# Main.net
KiCad netlist of a schematic drawn in Altium Designer
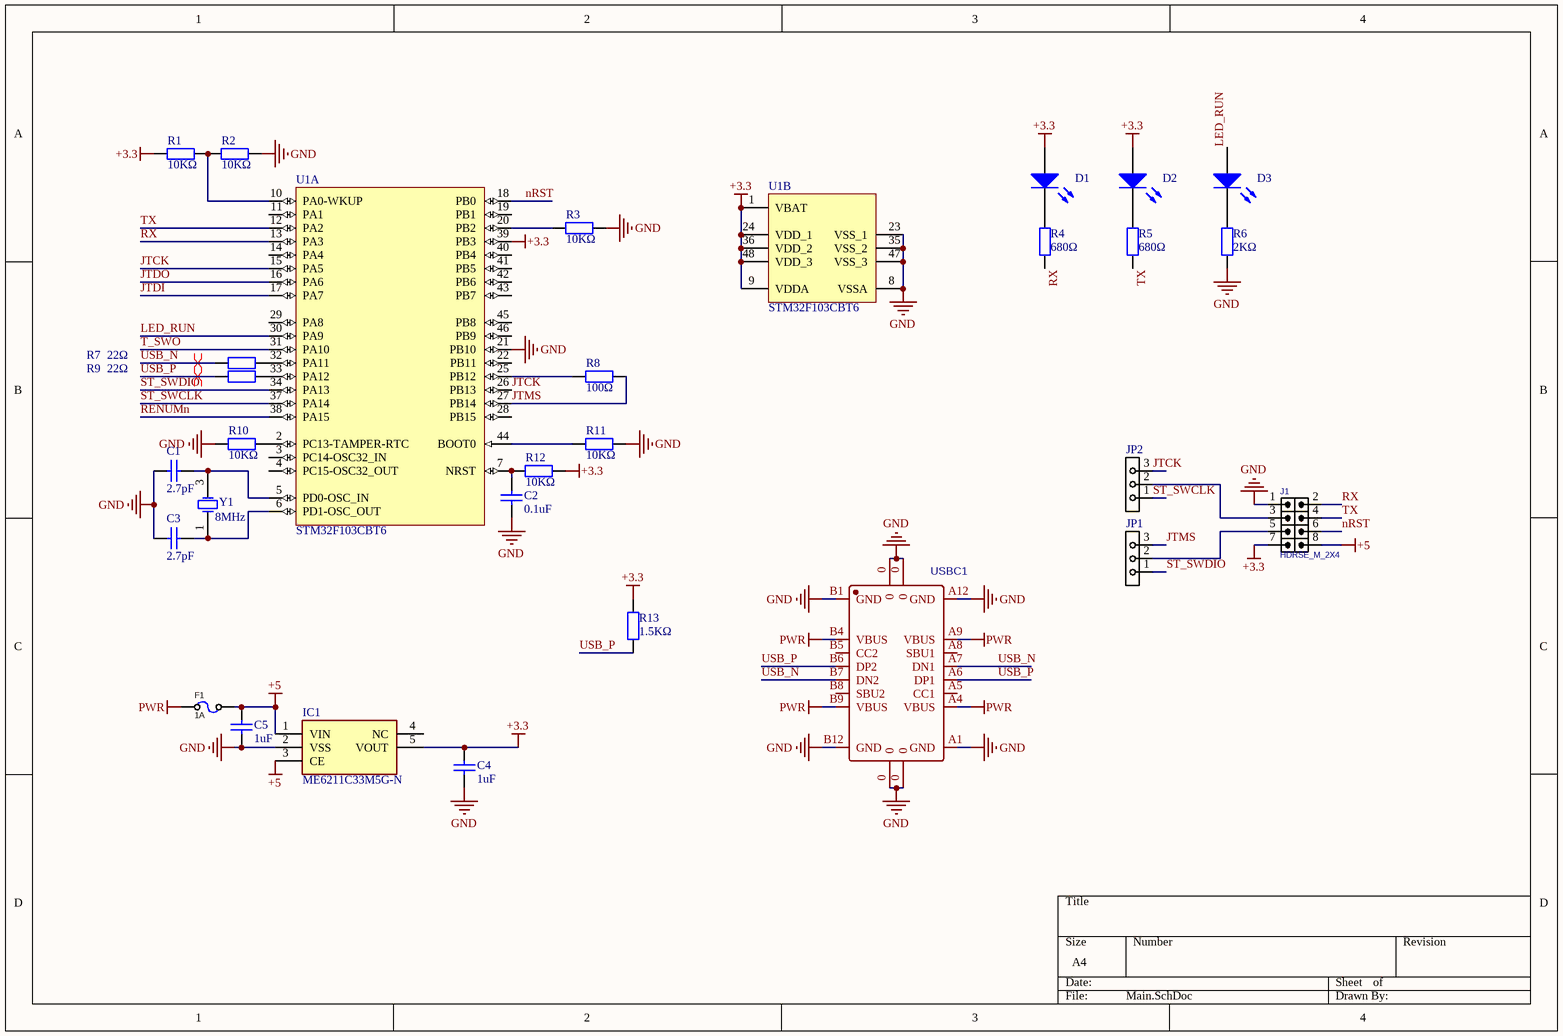
[diagram p0: Main.SchDoc]

(export (version "E")
  (design (tool "Eeschema 10.0.6"))
  (components
    (comp (ref "C1")
      (value "2.7pF")
      (footprint "0603_C")
      (description "贴片电容")
      (libsource (lib "Gaby's Workspace") (part "Symbol"))
    )
    (comp (ref "C2")
      (value "0.1uF")
      (footprint "0603_C")
      (description "贴片电容")
      (libsource (lib "Gaby's Workspace") (part "Symbol"))
    )
    (comp (ref "C3")
      (value "2.7pF")
      (footprint "0603_C")
      (description "贴片电容")
      (libsource (lib "Gaby's Workspace") (part "Symbol"))
    )
    (comp (ref "C4")
      (value "1uF")
      (footprint "0603_C")
      (description "贴片电容")
      (libsource (lib "Gaby's Workspace") (part "Symbol"))
    )
    (comp (ref "C5")
      (value "1uF")
      (footprint "0603_C")
      (description "贴片电容")
      (libsource (lib "Gaby's Workspace") (part "Symbol"))
    )
    (comp (ref "D1")
      (value "~")
      (footprint "0603_LED_S1")
      (description "发光二极管")
      (libsource (lib "") (part "Symbol_2"))
    )
    (comp (ref "D2")
      (value "~")
      (footprint "0603_LED_S1")
      (description "发光二极管")
      (libsource (lib "") (part "Symbol_2"))
    )
    (comp (ref "D3")
      (value "~")
      (footprint "0603_LED_S1")
      (description "发光二极管")
      (libsource (lib "") (part "Symbol_2"))
    )
    (comp (ref "F1")
      (value "1A")
      (footprint "F0805")
      (fields
        (field (name "MANF") "MANF")
        (field (name "MANF_P#") "MANF_PART#")
        (field (name "SOURCE") "protect_tvs_esd_fuse.SchLib")
      )
      (libsource (lib "") (part "Symbol_5"))
    )
    (comp (ref "IC1")
      (value "ME6211C33M5G-N")
      (footprint "SOT95P270X145-5N")
      (description "Integrated Circuit")
      (libsource (lib "Gaby's Workspace") (part "ME6211C33M5G-N"))
    )
    (comp (ref "J1")
      (value "HDRSE_M_2X4")
      (footprint "HDRSE_M_2X4")
      (description "CONN, HEADER, Male, pitch: 2.54mm, 8POS")
      (fields
        (field (name "MANF_P#") "MANF_PART#")
        (field (name "MANF") "MANF")
        (field (name "SOURCE") "conn_header_2.54_st_smd_edge.SchLib")
      )
      (libsource (lib "Gaby's Workspace") (part "HDRSE_M_2X4"))
    )
    (comp (ref "JP1")
      (value "JUMPER_SOLDER_3P")
      (footprint "JP_3_60W")
      (description "JUMPER, HEADER 3PIN")
      (fields (field (name "MANF") "MANF") (field (name "MANF_P#") "MANF_P#"))
      (libsource (lib "") (part "Symbol_7"))
    )
    (comp (ref "JP2")
      (value "JUMPER_SOLDER_3P")
      (footprint "JP_3_60W")
      (description "JUMPER, HEADER 3PIN")
      (fields (field (name "MANF") "MANF") (field (name "MANF_P#") "MANF_P#"))
      (libsource (lib "") (part "Symbol_7"))
    )
    (comp (ref "R1")
      (value "10KΩ")
      (footprint "0603_R")
      (description "贴片电阻")
      (libsource (lib "") (part "Symbol_3"))
    )
    (comp (ref "R2")
      (value "10KΩ")
      (footprint "0603_R")
      (description "贴片电阻")
      (libsource (lib "") (part "Symbol_3"))
    )
    (comp (ref "R3")
      (value "10KΩ")
      (footprint "0603_R")
      (description "贴片电阻")
      (libsource (lib "") (part "Symbol_3"))
    )
    (comp (ref "R4")
      (value "680Ω")
      (footprint "0603_R")
      (description "贴片电阻")
      (libsource (lib "") (part "Symbol_4"))
    )
    (comp (ref "R5")
      (value "680Ω")
      (footprint "0603_R")
      (description "贴片电阻")
      (libsource (lib "") (part "Symbol_4"))
    )
    (comp (ref "R6")
      (value "2KΩ")
      (footprint "0603_R")
      (description "贴片电阻")
      (libsource (lib "") (part "Symbol_4"))
    )
    (comp (ref "R7")
      (value "22Ω")
      (footprint "0603_R")
      (description "贴片电阻")
      (libsource (lib "") (part "Symbol_3"))
    )
    (comp (ref "R8")
      (value "100Ω")
      (footprint "0603_R")
      (description "贴片电阻")
      (libsource (lib "") (part "Symbol_3"))
    )
    (comp (ref "R9")
      (value "22Ω")
      (footprint "0603_R")
      (description "贴片电阻")
      (libsource (lib "") (part "Symbol_3"))
    )
    (comp (ref "R10")
      (value "10KΩ")
      (footprint "0603_R")
      (description "贴片电阻")
      (libsource (lib "") (part "Symbol_3"))
    )
    (comp (ref "R11")
      (value "10KΩ")
      (footprint "0603_R")
      (description "贴片电阻")
      (libsource (lib "") (part "Symbol_3"))
    )
    (comp (ref "R12")
      (value "10KΩ")
      (footprint "0603_R")
      (description "贴片电阻")
      (libsource (lib "") (part "Symbol_3"))
    )
    (comp (ref "R13")
      (value "1.5KΩ")
      (footprint "0603_R")
      (description "贴片电阻")
      (libsource (lib "") (part "Symbol_4"))
    )
    (comp (ref "U1")
      (value "STM32F103CBT6")
      (footprint "STM-LQFP48_N")
      (libsource (lib "") (part "Symbol_1"))
    )
    (comp (ref "USBC1")
      (value "USB2.0 Type-C 16Pin母座")
      (footprint "USB-C-SMD_TYPE-C-USB-5")
      (description "USB2.0 Type-C 母座 16Pin")
      (fields (field (name "AUTHOR") "白一清"))
      (libsource (lib "Gaby's Workspace") (part "USB2.0 Type-C 16Pin母座"))
    )
    (comp (ref "Y1")
      (value "8MHz")
      (footprint "SMD-3225_4P")
      (description "贴片晶振")
      (libsource (lib "") (part "Symbol_6"))
    )
  )
  (nets
    (net (code "1") (name "+3.3") (class "Default")
      (node (ref "C4") (pin "2") (pinfunction "2_2") (pintype "passive"))
      (node (ref "D1") (pin "A") (pinfunction "A_A") (pintype "passive"))
      (node (ref "D2") (pin "A") (pinfunction "A_A") (pintype "passive"))
      (node (ref "IC1") (pin "5") (pinfunction "VOUT_5") (pintype "passive"))
      (node (ref "J1") (pin "7") (pinfunction "7_7") (pintype "passive"))
      (node (ref "R1") (pin "1") (pinfunction "1_1") (pintype "passive"))
      (node (ref "R12") (pin "2") (pinfunction "2_2") (pintype "passive"))
      (node (ref "R13") (pin "2") (pinfunction "2_2") (pintype "passive"))
      (node (ref "U1") (pin "1") (pinfunction "VBAT_1") (pintype "power_in"))
      (node (ref "U1") (pin "24") (pinfunction "VDD_1_24") (pintype "power_in"))
      (node (ref "U1") (pin "36") (pinfunction "VDD_2_36") (pintype "power_in"))
      (node (ref "U1") (pin "39") (pinfunction "PB3_39") (pintype "bidirectional"))
      (node (ref "U1") (pin "48") (pinfunction "VDD_3_48") (pintype "power_in"))
      (node (ref "U1") (pin "9") (pinfunction "VDDA_9") (pintype "power_in"))
    )
    (net (code "2") (name "+5") (class "Default")
      (node (ref "C5") (pin "2") (pinfunction "2_2") (pintype "passive"))
      (node (ref "F1") (pin "2") (pinfunction "2_2") (pintype "passive"))
      (node (ref "IC1") (pin "1") (pinfunction "VIN_1") (pintype "passive"))
      (node (ref "IC1") (pin "3") (pinfunction "CE_3") (pintype "passive"))
      (node (ref "J1") (pin "8") (pinfunction "8_8") (pintype "passive"))
    )
    (net (code "3") (name "/JTCK") (class "Default")
      (node (ref "JP2") (pin "3") (pinfunction "3_3") (pintype "passive"))
      (node (ref "U1") (pin "15") (pinfunction "PA5_15") (pintype "bidirectional"))
      (node (ref "U1") (pin "26") (pinfunction "PB13_26") (pintype "bidirectional"))
    )
    (net (code "4") (name "/JTDI") (class "Default")
      (node (ref "U1") (pin "17") (pinfunction "PA7_17") (pintype "bidirectional"))
    )
    (net (code "5") (name "/JTDO") (class "Default")
      (node (ref "U1") (pin "16") (pinfunction "PA6_16") (pintype "bidirectional"))
    )
    (net (code "6") (name "/JTMS") (class "Default")
      (node (ref "JP1") (pin "3") (pinfunction "3_3") (pintype "passive"))
      (node (ref "R8") (pin "2") (pinfunction "2_2") (pintype "passive"))
      (node (ref "U1") (pin "27") (pinfunction "PB14_27") (pintype "bidirectional"))
    )
    (net (code "7") (name "/LED_RUN") (class "Default")
      (node (ref "D3") (pin "A") (pinfunction "A_A") (pintype "passive"))
      (node (ref "U1") (pin "30") (pinfunction "PA9_30") (pintype "bidirectional"))
    )
    (net (code "8") (name "/RENUMn") (class "Default")
      (node (ref "U1") (pin "38") (pinfunction "PA15_38") (pintype "bidirectional"))
    )
    (net (code "9") (name "/RX") (class "Default")
      (node (ref "J1") (pin "2") (pinfunction "2_2") (pintype "passive"))
      (node (ref "R4") (pin "1") (pinfunction "1_1") (pintype "passive"))
      (node (ref "U1") (pin "13") (pinfunction "PA3_13") (pintype "bidirectional"))
    )
    (net (code "10") (name "/ST_SWCLK") (class "Default")
      (node (ref "JP2") (pin "1") (pinfunction "1_1") (pintype "passive"))
      (node (ref "U1") (pin "37") (pinfunction "PA14_37") (pintype "bidirectional"))
    )
    (net (code "11") (name "/ST_SWDIO") (class "Default")
      (node (ref "JP1") (pin "1") (pinfunction "1_1") (pintype "passive"))
      (node (ref "U1") (pin "34") (pinfunction "PA13_34") (pintype "bidirectional"))
    )
    (net (code "12") (name "/TX") (class "Default")
      (node (ref "J1") (pin "4") (pinfunction "4_4") (pintype "passive"))
      (node (ref "R5") (pin "1") (pinfunction "1_1") (pintype "passive"))
      (node (ref "U1") (pin "12") (pinfunction "PA2_12") (pintype "bidirectional"))
    )
    (net (code "13") (name "/T_SWO") (class "Default")
      (node (ref "U1") (pin "31") (pinfunction "PA10_31") (pintype "bidirectional"))
    )
    (net (code "14") (name "/USB_N") (class "Default")
      (node (ref "R7") (pin "1") (pinfunction "1_1") (pintype "passive"))
      (node (ref "USBC1") (pin "A7") (pinfunction "DN1_A7") (pintype "passive"))
      (node (ref "USBC1") (pin "B7") (pinfunction "DN2_B7") (pintype "passive"))
    )
    (net (code "15") (name "/USB_P") (class "Default")
      (node (ref "R13") (pin "1") (pinfunction "1_1") (pintype "passive"))
      (node (ref "R9") (pin "1") (pinfunction "1_1") (pintype "passive"))
      (node (ref "USBC1") (pin "A6") (pinfunction "DP1_A6") (pintype "passive"))
      (node (ref "USBC1") (pin "B6") (pinfunction "DP2_B6") (pintype "passive"))
    )
    (net (code "16") (name "/nRST") (class "Default")
      (node (ref "J1") (pin "6") (pinfunction "6_6") (pintype "passive"))
      (node (ref "U1") (pin "18") (pinfunction "PB0_18") (pintype "bidirectional"))
    )
    (net (code "17") (name "GND") (class "Default")
      (node (ref "C1") (pin "1") (pinfunction "1_1") (pintype "passive"))
      (node (ref "C2") (pin "1") (pinfunction "1_1") (pintype "passive"))
      (node (ref "C3") (pin "1") (pinfunction "1_1") (pintype "passive"))
      (node (ref "C4") (pin "1") (pinfunction "1_1") (pintype "passive"))
      (node (ref "C5") (pin "1") (pinfunction "1_1") (pintype "passive"))
      (node (ref "IC1") (pin "2") (pinfunction "VSS_2") (pintype "passive"))
      (node (ref "J1") (pin "1") (pinfunction "1_1") (pintype "passive"))
      (node (ref "R10") (pin "1") (pinfunction "1_1") (pintype "passive"))
      (node (ref "R11") (pin "2") (pinfunction "2_2") (pintype "passive"))
      (node (ref "R2") (pin "2") (pinfunction "2_2") (pintype "passive"))
      (node (ref "R3") (pin "2") (pinfunction "2_2") (pintype "passive"))
      (node (ref "R6") (pin "1") (pinfunction "1_1") (pintype "passive"))
      (node (ref "U1") (pin "21") (pinfunction "PB10_21") (pintype "bidirectional"))
      (node (ref "U1") (pin "23") (pinfunction "VSS_1_23") (pintype "power_in"))
      (node (ref "U1") (pin "35") (pinfunction "VSS_2_35") (pintype "power_in"))
      (node (ref "U1") (pin "47") (pinfunction "VSS_3_47") (pintype "power_in"))
      (node (ref "U1") (pin "8") (pinfunction "VSSA_8") (pintype "power_in"))
      (node (ref "USBC1") (pin "0") (pinfunction "0_0") (pintype "passive"))
      (node (ref "USBC1") (pin "A1") (pinfunction "GND_A1") (pintype "passive"))
      (node (ref "USBC1") (pin "A12") (pinfunction "GND_A12") (pintype "passive"))
      (node (ref "USBC1") (pin "B1") (pinfunction "GND_B1") (pintype "passive"))
      (node (ref "USBC1") (pin "B12") (pinfunction "GND_B12") (pintype "passive"))
    )
    (net (code "18") (name "Net-(D1-PadK)") (class "Default")
      (node (ref "D1") (pin "K") (pinfunction "K_K") (pintype "passive"))
      (node (ref "R4") (pin "2") (pinfunction "2_2") (pintype "passive"))
    )
    (net (code "19") (name "Net-(D2-PadK)") (class "Default")
      (node (ref "D2") (pin "K") (pinfunction "K_K") (pintype "passive"))
      (node (ref "R5") (pin "2") (pinfunction "2_2") (pintype "passive"))
    )
    (net (code "20") (name "Net-(D3-PadK)") (class "Default")
      (node (ref "D3") (pin "K") (pinfunction "K_K") (pintype "passive"))
      (node (ref "R6") (pin "2") (pinfunction "2_2") (pintype "passive"))
    )
    (net (code "21") (name "Net-(J1-Pad3)") (class "Default")
      (node (ref "J1") (pin "3") (pinfunction "3_3") (pintype "passive"))
      (node (ref "JP2") (pin "2") (pinfunction "2_2") (pintype "passive"))
    )
    (net (code "22") (name "Net-(J1-Pad5)") (class "Default")
      (node (ref "J1") (pin "5") (pinfunction "5_5") (pintype "passive"))
      (node (ref "JP1") (pin "2") (pinfunction "2_2") (pintype "passive"))
    )
    (net (code "23") (name "Net-(U1A-BOOT0)") (class "Default")
      (node (ref "R11") (pin "1") (pinfunction "1_1") (pintype "passive"))
      (node (ref "U1") (pin "44") (pinfunction "BOOT0_44") (pintype "input"))
    )
    (net (code "24") (name "Net-(U1A-NRST)") (class "Default")
      (node (ref "C2") (pin "2") (pinfunction "2_2") (pintype "passive"))
      (node (ref "R12") (pin "1") (pinfunction "1_1") (pintype "passive"))
      (node (ref "U1") (pin "7") (pinfunction "NRST_7") (pintype "bidirectional"))
    )
    (net (code "25") (name "Net-(U1A-PA0-WKUP)") (class "Default")
      (node (ref "R1") (pin "2") (pinfunction "2_2") (pintype "passive"))
      (node (ref "R2") (pin "1") (pinfunction "1_1") (pintype "passive"))
      (node (ref "U1") (pin "10") (pinfunction "PA0-WKUP_10") (pintype "bidirectional"))
    )
    (net (code "26") (name "Net-(U1A-PA11)") (class "Default")
      (node (ref "R7") (pin "2") (pinfunction "2_2") (pintype "passive"))
      (node (ref "U1") (pin "32") (pinfunction "PA11_32") (pintype "bidirectional"))
    )
    (net (code "27") (name "Net-(U1A-PA12)") (class "Default")
      (node (ref "R9") (pin "2") (pinfunction "2_2") (pintype "passive"))
      (node (ref "U1") (pin "33") (pinfunction "PA12_33") (pintype "bidirectional"))
    )
    (net (code "28") (name "Net-(U1A-PB2)") (class "Default")
      (node (ref "R3") (pin "1") (pinfunction "1_1") (pintype "passive"))
      (node (ref "U1") (pin "20") (pinfunction "PB2_20") (pintype "bidirectional"))
    )
    (net (code "29") (name "Net-(U1A-PB12)") (class "Default")
      (node (ref "R8") (pin "1") (pinfunction "1_1") (pintype "passive"))
      (node (ref "U1") (pin "25") (pinfunction "PB12_25") (pintype "bidirectional"))
    )
    (net (code "30") (name "Net-(U1A-PC13-TAMPER-RTC)") (class "Default")
      (node (ref "R10") (pin "2") (pinfunction "2_2") (pintype "passive"))
      (node (ref "U1") (pin "2") (pinfunction "PC13-TAMPER-RTC_2") (pintype "bidirectional"))
    )
    (net (code "31") (name "Net-(U1A-PD0-OSC_IN)") (class "Default")
      (node (ref "C1") (pin "2") (pinfunction "2_2") (pintype "passive"))
      (node (ref "U1") (pin "5") (pinfunction "PD0-OSC_IN_5") (pintype "bidirectional"))
      (node (ref "Y1") (pin "3") (pinfunction "OSC2_3") (pintype "passive"))
    )
    (net (code "32") (name "Net-(U1A-PD1-OSC_OUT)") (class "Default")
      (node (ref "C3") (pin "2") (pinfunction "2_2") (pintype "passive"))
      (node (ref "U1") (pin "6") (pinfunction "PD1-OSC_OUT_6") (pintype "bidirectional"))
      (node (ref "Y1") (pin "1") (pinfunction "OSC1_1") (pintype "passive"))
    )
    (net (code "33") (name "PWR") (class "Default")
      (node (ref "F1") (pin "1") (pinfunction "1_1") (pintype "passive"))
      (node (ref "USBC1") (pin "A4") (pinfunction "VBUS_A4") (pintype "passive"))
      (node (ref "USBC1") (pin "A9") (pinfunction "VBUS_A9") (pintype "passive"))
      (node (ref "USBC1") (pin "B4") (pinfunction "VBUS_B4") (pintype "passive"))
      (node (ref "USBC1") (pin "B9") (pinfunction "VBUS_B9") (pintype "passive"))
    )
    (net (code "34") (name "unconnected-(IC1-NC-Pad4)") (class "Default")
      (node (ref "IC1") (pin "4") (pinfunction "NC_4") (pintype "passive"))
    )
    (net (code "35") (name "unconnected-(U1A-PA1-Pad11)") (class "Default")
      (node (ref "U1") (pin "11") (pinfunction "PA1_11") (pintype "bidirectional"))
    )
    (net (code "36") (name "unconnected-(U1A-PA4-Pad14)") (class "Default")
      (node (ref "U1") (pin "14") (pinfunction "PA4_14") (pintype "bidirectional"))
    )
    (net (code "37") (name "unconnected-(U1A-PA8-Pad29)") (class "Default")
      (node (ref "U1") (pin "29") (pinfunction "PA8_29") (pintype "bidirectional"))
    )
    (net (code "38") (name "unconnected-(U1A-PB1-Pad19)") (class "Default")
      (node (ref "U1") (pin "19") (pinfunction "PB1_19") (pintype "bidirectional"))
    )
    (net (code "39") (name "unconnected-(U1A-PB4-Pad40)") (class "Default")
      (node (ref "U1") (pin "40") (pinfunction "PB4_40") (pintype "bidirectional"))
    )
    (net (code "40") (name "unconnected-(U1A-PB5-Pad41)") (class "Default")
      (node (ref "U1") (pin "41") (pinfunction "PB5_41") (pintype "bidirectional"))
    )
    (net (code "41") (name "unconnected-(U1A-PB6-Pad42)") (class "Default")
      (node (ref "U1") (pin "42") (pinfunction "PB6_42") (pintype "bidirectional"))
    )
    (net (code "42") (name "unconnected-(U1A-PB7-Pad43)") (class "Default")
      (node (ref "U1") (pin "43") (pinfunction "PB7_43") (pintype "bidirectional"))
    )
    (net (code "43") (name "unconnected-(U1A-PB8-Pad45)") (class "Default")
      (node (ref "U1") (pin "45") (pinfunction "PB8_45") (pintype "bidirectional"))
    )
    (net (code "44") (name "unconnected-(U1A-PB9-Pad46)") (class "Default")
      (node (ref "U1") (pin "46") (pinfunction "PB9_46") (pintype "bidirectional"))
    )
    (net (code "45") (name "unconnected-(U1A-PB11-Pad22)") (class "Default")
      (node (ref "U1") (pin "22") (pinfunction "PB11_22") (pintype "bidirectional"))
    )
    (net (code "46") (name "unconnected-(U1A-PB15-Pad28)") (class "Default")
      (node (ref "U1") (pin "28") (pinfunction "PB15_28") (pintype "bidirectional"))
    )
    (net (code "47") (name "unconnected-(U1A-PC14-OSC32_IN-Pad3)") (class "Default")
      (node (ref "U1") (pin "3") (pinfunction "PC14-OSC32_IN_3") (pintype "bidirectional"))
    )
    (net (code "48") (name "unconnected-(U1A-PC15-OSC32_OUT-Pad4)") (class "Default")
      (node (ref "U1") (pin "4") (pinfunction "PC15-OSC32_OUT_4") (pintype "bidirectional"))
    )
    (net (code "49") (name "unconnected-(USBC1-CC1-PadA5)") (class "Default")
      (node (ref "USBC1") (pin "A5") (pinfunction "CC1_A5") (pintype "passive"))
    )
    (net (code "50") (name "unconnected-(USBC1-CC2-PadB5)") (class "Default")
      (node (ref "USBC1") (pin "B5") (pinfunction "CC2_B5") (pintype "passive"))
    )
    (net (code "51") (name "unconnected-(USBC1-SBU1-PadA8)") (class "Default")
      (node (ref "USBC1") (pin "A8") (pinfunction "SBU1_A8") (pintype "passive"))
    )
    (net (code "52") (name "unconnected-(USBC1-SBU2-PadB8)") (class "Default")
      (node (ref "USBC1") (pin "B8") (pinfunction "SBU2_B8") (pintype "passive"))
    )
  )
)
